# Sheet_bck.net
KiCad netlist of a schematic drawn in Altium Designer
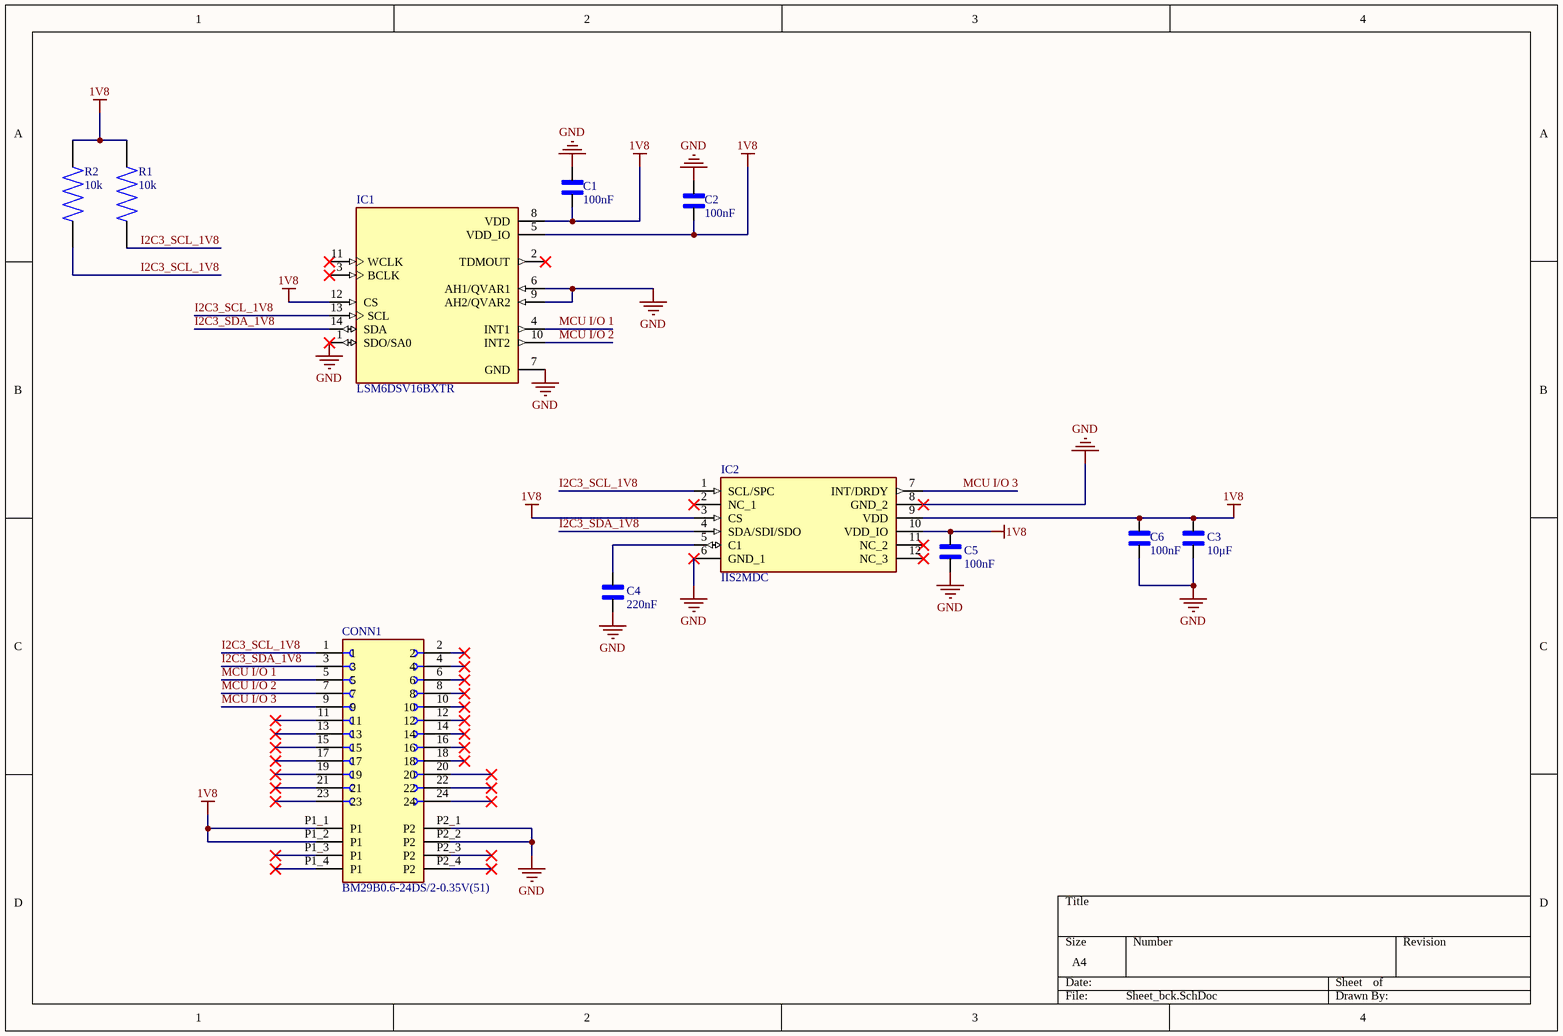
[diagram p0: Sheet_bck.SchDoc]

(export (version "E")
  (design (tool "Eeschema 10.0.6"))
  (components
    (comp (ref "C1")
      (value "100nF")
      (footprint "CAPC1005X55N")
      (description "0.1uF 10V 20% Multilayer Ceramic Capacitor X7R 0402 (1005 Metric)")
      (fields (field (name "MF") "Taiyo Yuden") (field (name "MP") "MMASL105SB7104MFNA18"))
      (libsource (lib "Schlib1") (part "MMASL105SB7104MFNA18"))
    )
    (comp (ref "C2")
      (value "100nF")
      (footprint "CAPC1005X55N")
      (description "0.1uF 10V 20% Multilayer Ceramic Capacitor X7R 0402 (1005 Metric)")
      (fields (field (name "MF") "Taiyo Yuden") (field (name "MP") "MMASL105SB7104MFNA18"))
      (libsource (lib "Schlib1") (part "MMASL105SB7104MFNA18"))
    )
    (comp (ref "C3")
      (value "10μF")
      (footprint "C10uf - CC0805KRX5R6BB106")
      (libsource (lib "Schlib1") (part "C 10uF"))
    )
    (comp (ref "C4")
      (value "220nF")
      (footprint "CAPC1005X60N")
      (description "Cap Ceramic 0.22uF 25V X7R 10% Pad SMD 0402 Soft Termination 125C Automotive T/R")
      (fields (field (name "MF") "TDK") (field (name "MP") "CGA2B3X7R1E224K050BE"))
      (libsource (lib "Schlib1") (part "CGA2B3X7R1E224K050BE"))
    )
    (comp (ref "C5")
      (value "100nF")
      (footprint "C100nF - VJ0402G104KXQCW1BC")
      (libsource (lib "") (part "C 100nf_1"))
    )
    (comp (ref "C6")
      (value "100nF")
      (footprint "C100nF - VJ0402G104KXQCW1BC")
      (libsource (lib "Schlib1") (part "C 100nf"))
    )
    (comp (ref "CONN1")
      (value "BM29B0.6-24DS/2-0.35V(51)")
      (footprint "HRS_BM29B0.6-24DS/2-0.35V(51)")
      (description "26 (24 + 2 Power) Position Connector Receptacle, Center Strip Contacts Surface Mount Gold")
      (fields (field (name "MF") "Hirose Connector"))
      (libsource (lib "Schlib1") (part "BM29B0.6-24DS/2-0.35V(51)"))
    )
    (comp (ref "IC1")
      (value "LSM6DSV16BXTR")
      (footprint "PQFN50P250X300X74-14N")
      (description "Accelerometer, Gyroscope, Temperature, 6 Axis Sensor IÂ²C, I3Câ„ , SPI Output")
      (fields (field (name "MF") "STMicroelectronics"))
      (libsource (lib "Schlib1") (part "LSM6DSV16BXTR"))
    )
    (comp (ref "IC2")
      (value "IIS2MDC")
      (footprint "Magnetometer")
      (libsource (lib "Schlib1") (part "IIS2MDC"))
    )
    (comp (ref "R1")
      (value "10k")
      (footprint "RESC1005X37N")
      (description "10 kOhms Â±1% 0.063W, 1/16W Chip Resistor 0402 (1005 Metric) Moisture Resistant Thick Film")
      (fields (field (name "MF") "Yageo") (field (name "MP") "RE0402FRE0710KL"))
      (libsource (lib "Schlib1") (part "RE0402FRE0710KL"))
    )
    (comp (ref "R2")
      (value "10k")
      (footprint "RESC1005X37N")
      (description "10 kOhms Â±1% 0.063W, 1/16W Chip Resistor 0402 (1005 Metric) Moisture Resistant Thick Film")
      (fields (field (name "MF") "Yageo") (field (name "MP") "RE0402FRE0710KL"))
      (libsource (lib "Schlib1") (part "RE0402FRE0710KL"))
    )
  )
  (nets
    (net (code "1") (name "/I2C3_SCL_1V8") (class "Default")
      (node (ref "CONN1") (pin "1") (pinfunction "1_1") (pintype "passive"))
      (node (ref "IC1") (pin "13") (pinfunction "SCL_13") (pintype "input"))
      (node (ref "IC2") (pin "1") (pinfunction "SCL/SPC_1") (pintype "input"))
      (node (ref "R1") (pin "2") (pinfunction "2_2") (pintype "passive"))
      (node (ref "R2") (pin "2") (pinfunction "2_2") (pintype "passive"))
    )
    (net (code "2") (name "/I2C3_SDA_1V8") (class "Default")
      (node (ref "CONN1") (pin "3") (pinfunction "3_3") (pintype "passive"))
      (node (ref "IC1") (pin "14") (pinfunction "SDA_14") (pintype "bidirectional"))
      (node (ref "IC2") (pin "4") (pinfunction "SDA/SDI/SDO_4") (pintype "input"))
    )
    (net (code "3") (name "/MCU I{slash}O 1") (class "Default")
      (node (ref "CONN1") (pin "5") (pinfunction "5_5") (pintype "passive"))
      (node (ref "IC1") (pin "4") (pinfunction "INT1_4") (pintype "output"))
    )
    (net (code "4") (name "/MCU I{slash}O 2") (class "Default")
      (node (ref "CONN1") (pin "7") (pinfunction "7_7") (pintype "passive"))
      (node (ref "IC1") (pin "10") (pinfunction "INT2_10") (pintype "output"))
    )
    (net (code "5") (name "/MCU I{slash}O 3") (class "Default")
      (node (ref "CONN1") (pin "9") (pinfunction "9_9") (pintype "passive"))
      (node (ref "IC2") (pin "7") (pinfunction "INT/DRDY_7") (pintype "output"))
    )
    (net (code "6") (name "1V8") (class "Default")
      (node (ref "C1") (pin "1") (pinfunction "1_1") (pintype "passive"))
      (node (ref "C2") (pin "1") (pinfunction "1_1") (pintype "passive"))
      (node (ref "C3") (pin "1") (pinfunction "1_1") (pintype "passive"))
      (node (ref "C5") (pin "2") (pinfunction "2_2") (pintype "passive"))
      (node (ref "C6") (pin "1") (pinfunction "1_1") (pintype "passive"))
      (node (ref "CONN1") (pin "P1_1") (pinfunction "P1_P1_1") (pintype "power_in"))
      (node (ref "CONN1") (pin "P1_2") (pinfunction "P1_P1_2") (pintype "power_in"))
      (node (ref "IC1") (pin "12") (pinfunction "CS_12") (pintype "input"))
      (node (ref "IC1") (pin "5") (pinfunction "VDD_IO_5") (pintype "power_in"))
      (node (ref "IC1") (pin "8") (pinfunction "VDD_8") (pintype "power_in"))
      (node (ref "IC2") (pin "10") (pinfunction "VDD_IO_10") (pintype "power_in"))
      (node (ref "IC2") (pin "3") (pinfunction "CS_3") (pintype "input"))
      (node (ref "IC2") (pin "9") (pinfunction "VDD_9") (pintype "power_in"))
      (node (ref "R1") (pin "1") (pinfunction "1_1") (pintype "passive"))
      (node (ref "R2") (pin "1") (pinfunction "1_1") (pintype "passive"))
    )
    (net (code "7") (name "GND") (class "Default")
      (node (ref "C1") (pin "2") (pinfunction "2_2") (pintype "passive"))
      (node (ref "C2") (pin "2") (pinfunction "2_2") (pintype "passive"))
      (node (ref "C3") (pin "2") (pinfunction "2_2") (pintype "passive"))
      (node (ref "C4") (pin "1") (pinfunction "1_1") (pintype "passive"))
      (node (ref "C5") (pin "1") (pinfunction "1_1") (pintype "passive"))
      (node (ref "C6") (pin "2") (pinfunction "2_2") (pintype "passive"))
      (node (ref "CONN1") (pin "P2_1") (pinfunction "P2_P2_1") (pintype "power_in"))
      (node (ref "CONN1") (pin "P2_2") (pinfunction "P2_P2_2") (pintype "power_in"))
      (node (ref "IC1") (pin "1") (pinfunction "SDO/SA0_1") (pintype "bidirectional"))
      (node (ref "IC1") (pin "6") (pinfunction "AH1/QVAR1_6") (pintype "input"))
      (node (ref "IC1") (pin "7") (pinfunction "GND_7") (pintype "power_in"))
      (node (ref "IC1") (pin "9") (pinfunction "AH2/QVAR2_9") (pintype "input"))
      (node (ref "IC2") (pin "6") (pinfunction "GND_1_6") (pintype "power_in"))
      (node (ref "IC2") (pin "8") (pinfunction "GND_2_8") (pintype "power_in"))
    )
    (net (code "8") (name "Net-(IC2-C1)") (class "Default")
      (node (ref "C4") (pin "2") (pinfunction "2_2") (pintype "passive"))
      (node (ref "IC2") (pin "5") (pinfunction "C1_5") (pintype "bidirectional"))
    )
    (net (code "9") (name "unconnected-(CONN1-P1-PadP1_3)") (class "Default")
      (node (ref "CONN1") (pin "P1_3") (pinfunction "P1_P1_3") (pintype "power_in+no_connect"))
    )
    (net (code "10") (name "unconnected-(CONN1-P1-PadP1_4)") (class "Default")
      (node (ref "CONN1") (pin "P1_4") (pinfunction "P1_P1_4") (pintype "power_in+no_connect"))
    )
    (net (code "11") (name "unconnected-(CONN1-P2-PadP2_3)") (class "Default")
      (node (ref "CONN1") (pin "P2_3") (pinfunction "P2_P2_3") (pintype "power_in+no_connect"))
    )
    (net (code "12") (name "unconnected-(CONN1-P2-PadP2_4)") (class "Default")
      (node (ref "CONN1") (pin "P2_4") (pinfunction "P2_P2_4") (pintype "power_in+no_connect"))
    )
    (net (code "13") (name "unconnected-(CONN1-Pad2)") (class "Default")
      (node (ref "CONN1") (pin "2") (pinfunction "2_2") (pintype "passive+no_connect"))
    )
    (net (code "14") (name "unconnected-(CONN1-Pad4)") (class "Default")
      (node (ref "CONN1") (pin "4") (pinfunction "4_4") (pintype "passive+no_connect"))
    )
    (net (code "15") (name "unconnected-(CONN1-Pad6)") (class "Default")
      (node (ref "CONN1") (pin "6") (pinfunction "6_6") (pintype "passive+no_connect"))
    )
    (net (code "16") (name "unconnected-(CONN1-Pad8)") (class "Default")
      (node (ref "CONN1") (pin "8") (pinfunction "8_8") (pintype "passive+no_connect"))
    )
    (net (code "17") (name "unconnected-(CONN1-Pad10)") (class "Default")
      (node (ref "CONN1") (pin "10") (pinfunction "10_10") (pintype "passive+no_connect"))
    )
    (net (code "18") (name "unconnected-(CONN1-Pad11)") (class "Default")
      (node (ref "CONN1") (pin "11") (pinfunction "11_11") (pintype "passive+no_connect"))
    )
    (net (code "19") (name "unconnected-(CONN1-Pad12)") (class "Default")
      (node (ref "CONN1") (pin "12") (pinfunction "12_12") (pintype "passive+no_connect"))
    )
    (net (code "20") (name "unconnected-(CONN1-Pad13)") (class "Default")
      (node (ref "CONN1") (pin "13") (pinfunction "13_13") (pintype "passive+no_connect"))
    )
    (net (code "21") (name "unconnected-(CONN1-Pad14)") (class "Default")
      (node (ref "CONN1") (pin "14") (pinfunction "14_14") (pintype "passive+no_connect"))
    )
    (net (code "22") (name "unconnected-(CONN1-Pad15)") (class "Default")
      (node (ref "CONN1") (pin "15") (pinfunction "15_15") (pintype "passive+no_connect"))
    )
    (net (code "23") (name "unconnected-(CONN1-Pad16)") (class "Default")
      (node (ref "CONN1") (pin "16") (pinfunction "16_16") (pintype "passive+no_connect"))
    )
    (net (code "24") (name "unconnected-(CONN1-Pad17)") (class "Default")
      (node (ref "CONN1") (pin "17") (pinfunction "17_17") (pintype "passive+no_connect"))
    )
    (net (code "25") (name "unconnected-(CONN1-Pad18)") (class "Default")
      (node (ref "CONN1") (pin "18") (pinfunction "18_18") (pintype "passive+no_connect"))
    )
    (net (code "26") (name "unconnected-(CONN1-Pad19)") (class "Default")
      (node (ref "CONN1") (pin "19") (pinfunction "19_19") (pintype "passive+no_connect"))
    )
    (net (code "27") (name "unconnected-(CONN1-Pad20)") (class "Default")
      (node (ref "CONN1") (pin "20") (pinfunction "20_20") (pintype "passive+no_connect"))
    )
    (net (code "28") (name "unconnected-(CONN1-Pad21)") (class "Default")
      (node (ref "CONN1") (pin "21") (pinfunction "21_21") (pintype "passive+no_connect"))
    )
    (net (code "29") (name "unconnected-(CONN1-Pad22)") (class "Default")
      (node (ref "CONN1") (pin "22") (pinfunction "22_22") (pintype "passive+no_connect"))
    )
    (net (code "30") (name "unconnected-(CONN1-Pad23)") (class "Default")
      (node (ref "CONN1") (pin "23") (pinfunction "23_23") (pintype "passive+no_connect"))
    )
    (net (code "31") (name "unconnected-(CONN1-Pad24)") (class "Default")
      (node (ref "CONN1") (pin "24") (pinfunction "24_24") (pintype "passive+no_connect"))
    )
    (net (code "32") (name "unconnected-(IC1-BCLK-Pad3)") (class "Default")
      (node (ref "IC1") (pin "3") (pinfunction "BCLK_3") (pintype "input+no_connect"))
    )
    (net (code "33") (name "unconnected-(IC1-TDMOUT-Pad2)") (class "Default")
      (node (ref "IC1") (pin "2") (pinfunction "TDMOUT_2") (pintype "output+no_connect"))
    )
    (net (code "34") (name "unconnected-(IC1-WCLK-Pad11)") (class "Default")
      (node (ref "IC1") (pin "11") (pinfunction "WCLK_11") (pintype "input+no_connect"))
    )
    (net (code "35") (name "unconnected-(IC2-NC_1-Pad2)") (class "Default")
      (node (ref "IC2") (pin "2") (pinfunction "NC_1_2") (pintype "tri_state+no_connect"))
    )
    (net (code "36") (name "unconnected-(IC2-NC_2-Pad11)") (class "Default")
      (node (ref "IC2") (pin "11") (pinfunction "NC_2_11") (pintype "tri_state+no_connect"))
    )
    (net (code "37") (name "unconnected-(IC2-NC_3-Pad12)") (class "Default")
      (node (ref "IC2") (pin "12") (pinfunction "NC_3_12") (pintype "tri_state+no_connect"))
    )
  )
)
